# Ring_4_B.net
KiCad netlist of a schematic drawn in Altium Designer
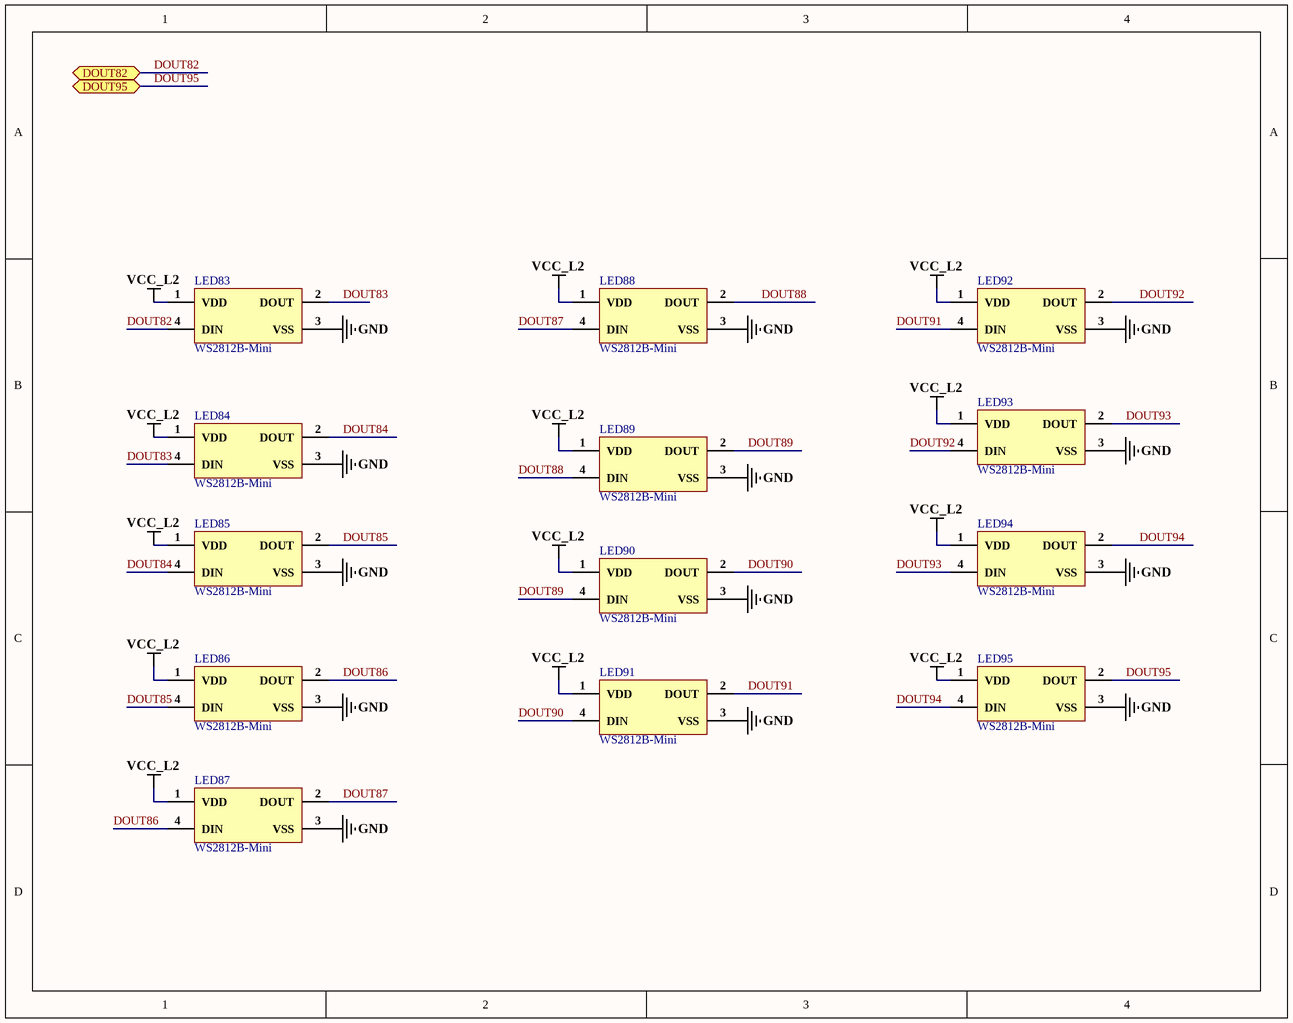
[diagram p0: Ring 4_B.SchDoc]

(export (version "E")
  (design (tool "Eeschema 10.0.6"))
  (components
    (comp (ref "LED83")
      (value "WS2812B-Mini")
      (footprint "WS2812B-Mini")
      (description "SMD,3.5x3.5mm Light Emitting Diodes (LED) RoHS")
      (fields (field (name "MANUFACTURER") "Worldsemi"))
      (libsource (lib "TT_IntLib") (part "WS2812B-Mini"))
    )
    (comp (ref "LED84")
      (value "WS2812B-Mini")
      (footprint "WS2812B-Mini")
      (description "SMD,3.5x3.5mm Light Emitting Diodes (LED) RoHS")
      (fields (field (name "MANUFACTURER") "Worldsemi"))
      (libsource (lib "TT_IntLib") (part "WS2812B-Mini"))
    )
    (comp (ref "LED85")
      (value "WS2812B-Mini")
      (footprint "WS2812B-Mini")
      (description "SMD,3.5x3.5mm Light Emitting Diodes (LED) RoHS")
      (fields (field (name "MANUFACTURER") "Worldsemi"))
      (libsource (lib "TT_IntLib") (part "WS2812B-Mini"))
    )
    (comp (ref "LED86")
      (value "WS2812B-Mini")
      (footprint "WS2812B-Mini")
      (description "SMD,3.5x3.5mm Light Emitting Diodes (LED) RoHS")
      (fields (field (name "MANUFACTURER") "Worldsemi"))
      (libsource (lib "TT_IntLib") (part "WS2812B-Mini"))
    )
    (comp (ref "LED87")
      (value "WS2812B-Mini")
      (footprint "WS2812B-Mini")
      (description "SMD,3.5x3.5mm Light Emitting Diodes (LED) RoHS")
      (fields (field (name "MANUFACTURER") "Worldsemi"))
      (libsource (lib "TT_IntLib") (part "WS2812B-Mini"))
    )
    (comp (ref "LED88")
      (value "WS2812B-Mini")
      (footprint "WS2812B-Mini")
      (description "SMD,3.5x3.5mm Light Emitting Diodes (LED) RoHS")
      (fields (field (name "MANUFACTURER") "Worldsemi"))
      (libsource (lib "TT_IntLib") (part "WS2812B-Mini"))
    )
    (comp (ref "LED89")
      (value "WS2812B-Mini")
      (footprint "WS2812B-Mini")
      (description "SMD,3.5x3.5mm Light Emitting Diodes (LED) RoHS")
      (fields (field (name "MANUFACTURER") "Worldsemi"))
      (libsource (lib "TT_IntLib") (part "WS2812B-Mini"))
    )
    (comp (ref "LED90")
      (value "WS2812B-Mini")
      (footprint "WS2812B-Mini")
      (description "SMD,3.5x3.5mm Light Emitting Diodes (LED) RoHS")
      (fields (field (name "MANUFACTURER") "Worldsemi"))
      (libsource (lib "TT_IntLib") (part "WS2812B-Mini"))
    )
    (comp (ref "LED91")
      (value "WS2812B-Mini")
      (footprint "WS2812B-Mini")
      (description "SMD,3.5x3.5mm Light Emitting Diodes (LED) RoHS")
      (fields (field (name "MANUFACTURER") "Worldsemi"))
      (libsource (lib "TT_IntLib") (part "WS2812B-Mini"))
    )
    (comp (ref "LED92")
      (value "WS2812B-Mini")
      (footprint "WS2812B-Mini")
      (description "SMD,3.5x3.5mm Light Emitting Diodes (LED) RoHS")
      (fields (field (name "MANUFACTURER") "Worldsemi"))
      (libsource (lib "TT_IntLib") (part "WS2812B-Mini"))
    )
    (comp (ref "LED93")
      (value "WS2812B-Mini")
      (footprint "WS2812B-Mini")
      (description "SMD,3.5x3.5mm Light Emitting Diodes (LED) RoHS")
      (fields (field (name "MANUFACTURER") "Worldsemi"))
      (libsource (lib "TT_IntLib") (part "WS2812B-Mini"))
    )
    (comp (ref "LED94")
      (value "WS2812B-Mini")
      (footprint "WS2812B-Mini")
      (description "SMD,3.5x3.5mm Light Emitting Diodes (LED) RoHS")
      (fields (field (name "MANUFACTURER") "Worldsemi"))
      (libsource (lib "TT_IntLib") (part "WS2812B-Mini"))
    )
    (comp (ref "LED95")
      (value "WS2812B-Mini")
      (footprint "WS2812B-Mini")
      (description "SMD,3.5x3.5mm Light Emitting Diodes (LED) RoHS")
      (fields (field (name "MANUFACTURER") "Worldsemi"))
      (libsource (lib "TT_IntLib") (part "WS2812B-Mini"))
    )
  )
  (nets
    (net (code "1") (name "/DOUT82") (class "Default")
      (node (ref "LED83") (pin "4") (pinfunction "DIN_4") (pintype "passive"))
    )
    (net (code "2") (name "/DOUT83") (class "Default")
      (node (ref "LED83") (pin "2") (pinfunction "DOUT_2") (pintype "passive"))
      (node (ref "LED84") (pin "4") (pinfunction "DIN_4") (pintype "passive"))
    )
    (net (code "3") (name "/DOUT84") (class "Default")
      (node (ref "LED84") (pin "2") (pinfunction "DOUT_2") (pintype "passive"))
      (node (ref "LED85") (pin "4") (pinfunction "DIN_4") (pintype "passive"))
    )
    (net (code "4") (name "/DOUT85") (class "Default")
      (node (ref "LED85") (pin "2") (pinfunction "DOUT_2") (pintype "passive"))
      (node (ref "LED86") (pin "4") (pinfunction "DIN_4") (pintype "passive"))
    )
    (net (code "5") (name "/DOUT86") (class "Default")
      (node (ref "LED86") (pin "2") (pinfunction "DOUT_2") (pintype "passive"))
      (node (ref "LED87") (pin "4") (pinfunction "DIN_4") (pintype "passive"))
    )
    (net (code "6") (name "/DOUT87") (class "Default")
      (node (ref "LED87") (pin "2") (pinfunction "DOUT_2") (pintype "passive"))
      (node (ref "LED88") (pin "4") (pinfunction "DIN_4") (pintype "passive"))
    )
    (net (code "7") (name "/DOUT88") (class "Default")
      (node (ref "LED88") (pin "2") (pinfunction "DOUT_2") (pintype "passive"))
      (node (ref "LED89") (pin "4") (pinfunction "DIN_4") (pintype "passive"))
    )
    (net (code "8") (name "/DOUT89") (class "Default")
      (node (ref "LED89") (pin "2") (pinfunction "DOUT_2") (pintype "passive"))
      (node (ref "LED90") (pin "4") (pinfunction "DIN_4") (pintype "passive"))
    )
    (net (code "9") (name "/DOUT90") (class "Default")
      (node (ref "LED90") (pin "2") (pinfunction "DOUT_2") (pintype "passive"))
      (node (ref "LED91") (pin "4") (pinfunction "DIN_4") (pintype "passive"))
    )
    (net (code "10") (name "/DOUT91") (class "Default")
      (node (ref "LED91") (pin "2") (pinfunction "DOUT_2") (pintype "passive"))
      (node (ref "LED92") (pin "4") (pinfunction "DIN_4") (pintype "passive"))
    )
    (net (code "11") (name "/DOUT92") (class "Default")
      (node (ref "LED92") (pin "2") (pinfunction "DOUT_2") (pintype "passive"))
      (node (ref "LED93") (pin "4") (pinfunction "DIN_4") (pintype "passive"))
    )
    (net (code "12") (name "/DOUT93") (class "Default")
      (node (ref "LED93") (pin "2") (pinfunction "DOUT_2") (pintype "passive"))
      (node (ref "LED94") (pin "4") (pinfunction "DIN_4") (pintype "passive"))
    )
    (net (code "13") (name "/DOUT94") (class "Default")
      (node (ref "LED94") (pin "2") (pinfunction "DOUT_2") (pintype "passive"))
      (node (ref "LED95") (pin "4") (pinfunction "DIN_4") (pintype "passive"))
    )
    (net (code "14") (name "/DOUT95") (class "Default")
      (node (ref "LED95") (pin "2") (pinfunction "DOUT_2") (pintype "passive"))
    )
    (net (code "15") (name "GND") (class "Default")
      (node (ref "LED83") (pin "3") (pinfunction "VSS_3") (pintype "passive"))
      (node (ref "LED84") (pin "3") (pinfunction "VSS_3") (pintype "passive"))
      (node (ref "LED85") (pin "3") (pinfunction "VSS_3") (pintype "passive"))
      (node (ref "LED86") (pin "3") (pinfunction "VSS_3") (pintype "passive"))
      (node (ref "LED87") (pin "3") (pinfunction "VSS_3") (pintype "passive"))
      (node (ref "LED88") (pin "3") (pinfunction "VSS_3") (pintype "passive"))
      (node (ref "LED89") (pin "3") (pinfunction "VSS_3") (pintype "passive"))
      (node (ref "LED90") (pin "3") (pinfunction "VSS_3") (pintype "passive"))
      (node (ref "LED91") (pin "3") (pinfunction "VSS_3") (pintype "passive"))
      (node (ref "LED92") (pin "3") (pinfunction "VSS_3") (pintype "passive"))
      (node (ref "LED93") (pin "3") (pinfunction "VSS_3") (pintype "passive"))
      (node (ref "LED94") (pin "3") (pinfunction "VSS_3") (pintype "passive"))
      (node (ref "LED95") (pin "3") (pinfunction "VSS_3") (pintype "passive"))
    )
    (net (code "16") (name "VCC_L2") (class "Default")
      (node (ref "LED83") (pin "1") (pinfunction "VDD_1") (pintype "passive"))
      (node (ref "LED84") (pin "1") (pinfunction "VDD_1") (pintype "passive"))
      (node (ref "LED85") (pin "1") (pinfunction "VDD_1") (pintype "passive"))
      (node (ref "LED86") (pin "1") (pinfunction "VDD_1") (pintype "passive"))
      (node (ref "LED87") (pin "1") (pinfunction "VDD_1") (pintype "passive"))
      (node (ref "LED88") (pin "1") (pinfunction "VDD_1") (pintype "passive"))
      (node (ref "LED89") (pin "1") (pinfunction "VDD_1") (pintype "passive"))
      (node (ref "LED90") (pin "1") (pinfunction "VDD_1") (pintype "passive"))
      (node (ref "LED91") (pin "1") (pinfunction "VDD_1") (pintype "passive"))
      (node (ref "LED92") (pin "1") (pinfunction "VDD_1") (pintype "passive"))
      (node (ref "LED93") (pin "1") (pinfunction "VDD_1") (pintype "passive"))
      (node (ref "LED94") (pin "1") (pinfunction "VDD_1") (pintype "passive"))
      (node (ref "LED95") (pin "1") (pinfunction "VDD_1") (pintype "passive"))
    )
  )
)
